# SampleCompact.net
KiCad netlist of a schematic drawn in Altium Designer
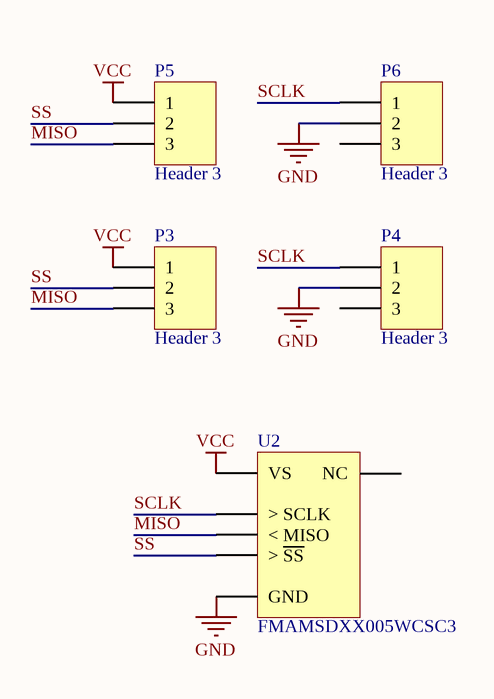
[diagram p0: SampleCompact.SchDoc]

(export (version "E")
  (design (tool "Eeschema 10.0.6"))
  (components
    (comp (ref "P3")
      (value "Header 3")
      (footprint "HDR1X3")
      (description "Header, 3-Pin")
      (fields (field (name "PUBLISHER") "Altium Limited"))
      (libsource (lib "FMA_Sensor") (part "Header 3"))
    )
    (comp (ref "P4")
      (value "Header 3")
      (footprint "HDR1X3")
      (description "Header, 3-Pin")
      (fields (field (name "PUBLISHER") "Altium Limited"))
      (libsource (lib "FMA_Sensor") (part "Header 3"))
    )
    (comp (ref "P5")
      (value "Header 3")
      (footprint "HDR1X3")
      (description "Header, 3-Pin")
      (fields (field (name "PUBLISHER") "Altium Limited"))
      (libsource (lib "FMA_Sensor") (part "Header 3"))
    )
    (comp (ref "P6")
      (value "Header 3")
      (footprint "HDR1X3")
      (description "Header, 3-Pin")
      (fields (field (name "PUBLISHER") "Altium Limited"))
      (libsource (lib "FMA_Sensor") (part "Header 3"))
    )
    (comp (ref "U2")
      (value "FMAMSDXX005WCSC3")
      (footprint "FMA_MICROFORCE_6")
      (libsource (lib "FMA_Sensor") (part "FMAMSDXX005WCSC3"))
    )
  )
  (nets
    (net (code "1") (name "/MISO") (class "Default")
      (node (ref "P3") (pin "3") (pinfunction "3_3") (pintype "passive"))
      (node (ref "P5") (pin "3") (pinfunction "3_3") (pintype "passive"))
      (node (ref "U2") (pin "5") (pinfunction "<_MISO_5") (pintype "passive"))
    )
    (net (code "2") (name "/SCLK") (class "Default")
      (node (ref "P4") (pin "1") (pinfunction "1_1") (pintype "passive"))
      (node (ref "P6") (pin "1") (pinfunction "1_1") (pintype "passive"))
      (node (ref "U2") (pin "4") (pinfunction ">_SCLK_4") (pintype "passive"))
    )
    (net (code "3") (name "/SS") (class "Default")
      (node (ref "P3") (pin "2") (pinfunction "2_2") (pintype "passive"))
      (node (ref "P5") (pin "2") (pinfunction "2_2") (pintype "passive"))
      (node (ref "U2") (pin "2") (pinfunction ">_~{SS}_2") (pintype "passive"))
    )
    (net (code "4") (name "GND") (class "Default")
      (node (ref "P4") (pin "2") (pinfunction "2_2") (pintype "passive"))
      (node (ref "P6") (pin "2") (pinfunction "2_2") (pintype "passive"))
      (node (ref "U2") (pin "3") (pinfunction "GND_3") (pintype "passive"))
    )
    (net (code "5") (name "VCC") (class "Default")
      (node (ref "P3") (pin "1") (pinfunction "1_1") (pintype "passive"))
      (node (ref "P5") (pin "1") (pinfunction "1_1") (pintype "passive"))
      (node (ref "U2") (pin "1") (pinfunction "VS_1") (pintype "passive"))
    )
    (net (code "6") (name "unconnected-(P4-Pad3)") (class "Default")
      (node (ref "P4") (pin "3") (pinfunction "3_3") (pintype "passive"))
    )
    (net (code "7") (name "unconnected-(P6-Pad3)") (class "Default")
      (node (ref "P6") (pin "3") (pinfunction "3_3") (pintype "passive"))
    )
    (net (code "8") (name "unconnected-(U2-NC-Pad6)") (class "Default")
      (node (ref "U2") (pin "6") (pinfunction "NC_6") (pintype "passive"))
    )
  )
)
